# EVGP_Estop_Motherboard.net
KiCad netlist of a schematic drawn in EAGLE
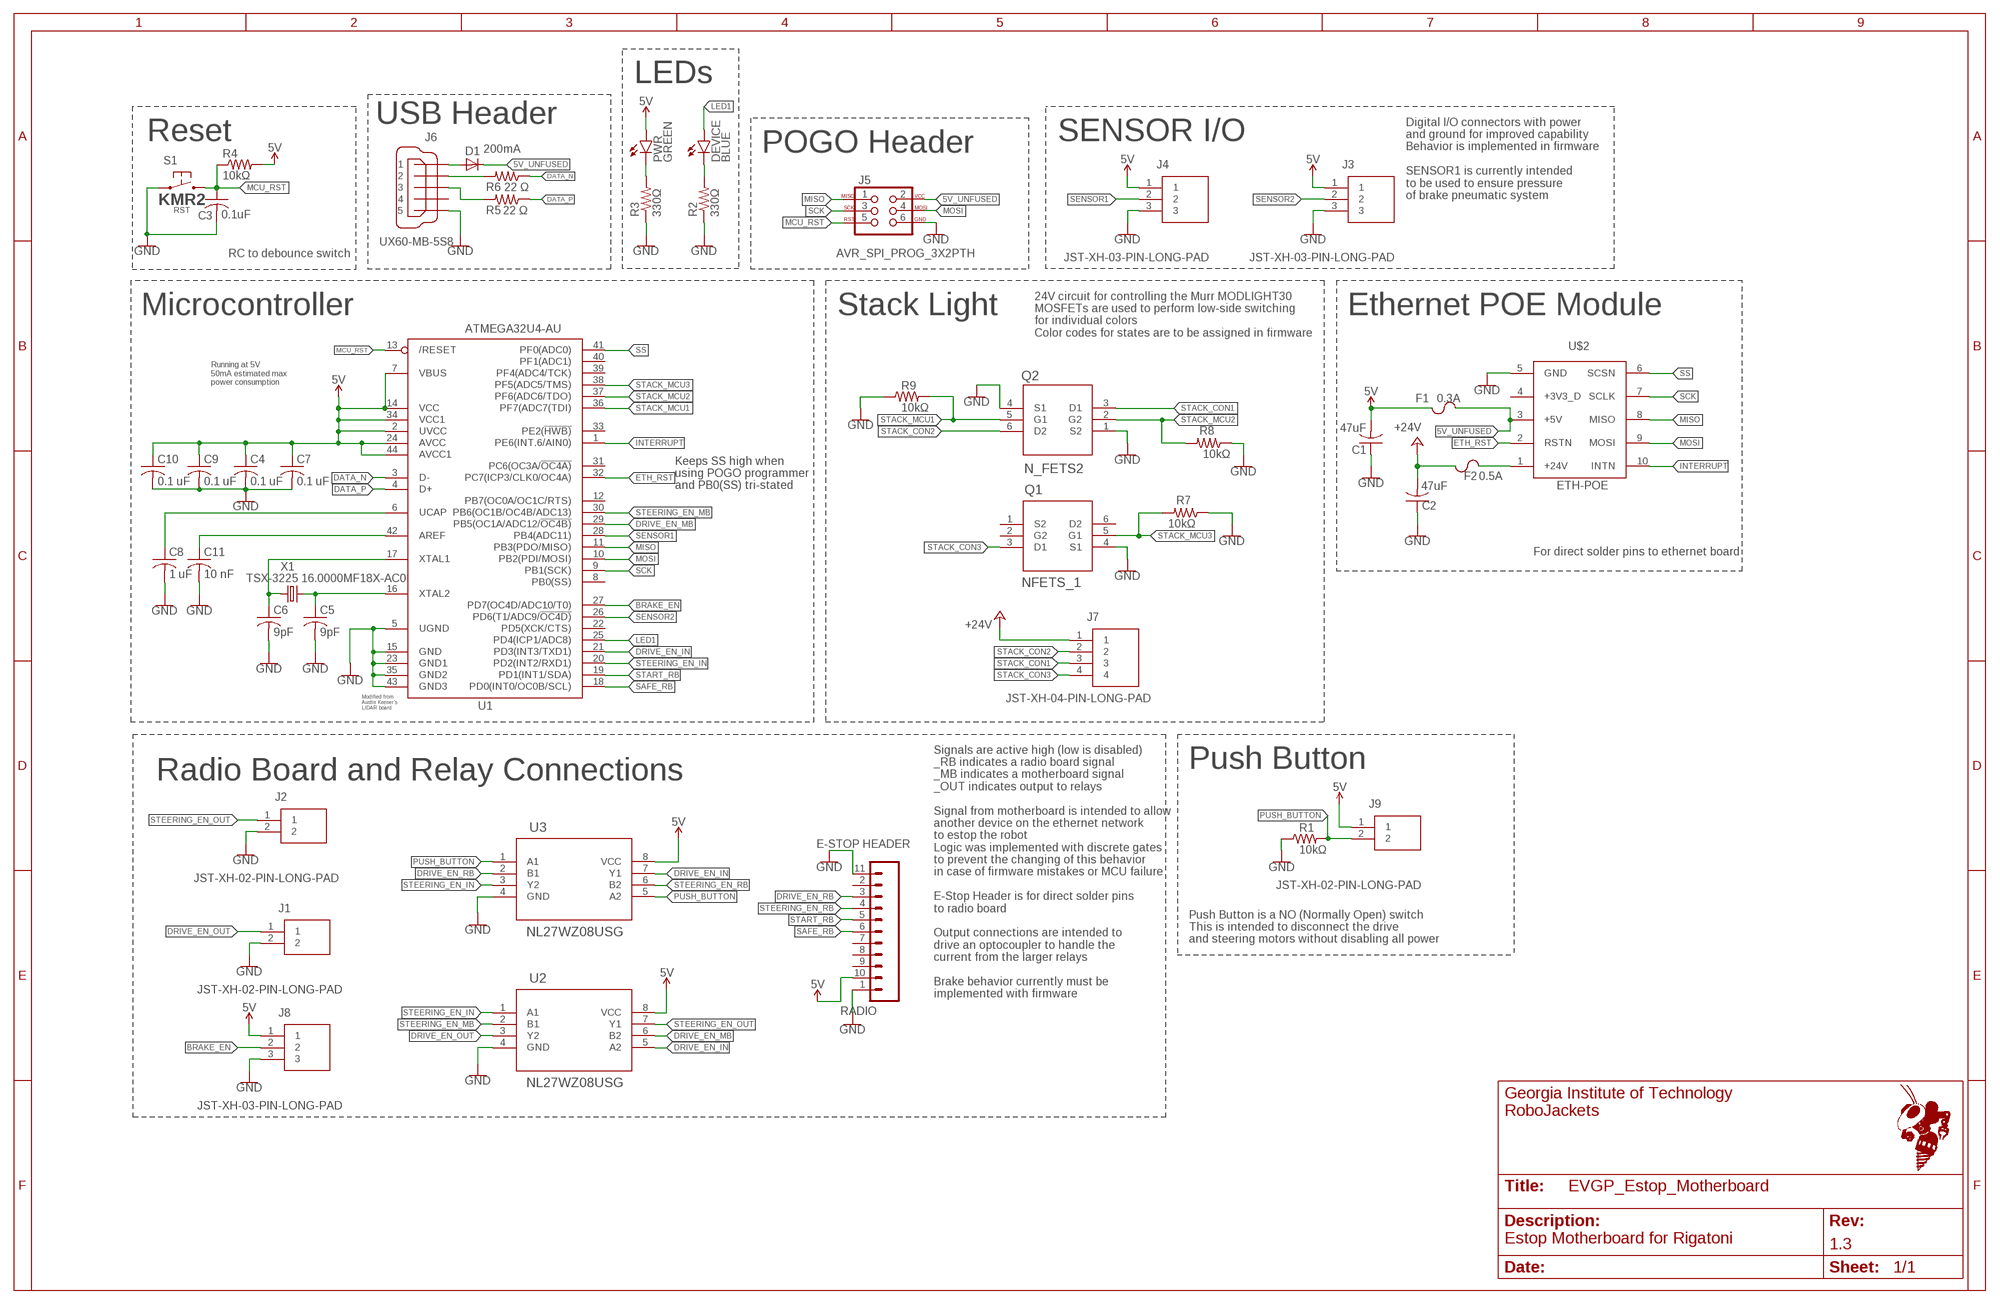
[diagram p0: schematic, sheet 1]

(export (version "E")
  (design (tool "Eeschema 10.0.6"))
  (components
    (comp (ref "C1")
      (value "47uF")
      (footprint "eagle-import:C1206")
      (libsource (lib "eagle-import") (part "C-USC1206"))
    )
    (comp (ref "C2")
      (value "47uF")
      (footprint "eagle-import:C1206")
      (libsource (lib "eagle-import") (part "C-USC1206"))
    )
    (comp (ref "C3")
      (value "0.1uF")
      (footprint "eagle-import:C0603")
      (libsource (lib "eagle-import") (part "C-USC0603"))
    )
    (comp (ref "C4")
      (value "0.1 uF")
      (footprint "eagle-import:C0603")
      (libsource (lib "eagle-import") (part "resistor_348_C-USC0603"))
    )
    (comp (ref "C5")
      (value "9pF")
      (footprint "eagle-import:C0603")
      (libsource (lib "eagle-import") (part "resistor_348_C-USC0603"))
    )
    (comp (ref "C6")
      (value "9pF")
      (footprint "eagle-import:C0603")
      (libsource (lib "eagle-import") (part "resistor_348_C-USC0603"))
    )
    (comp (ref "C7")
      (value "0.1 uF")
      (footprint "eagle-import:C0603")
      (libsource (lib "eagle-import") (part "resistor_348_C-USC0603"))
    )
    (comp (ref "C8")
      (value "1 uF")
      (footprint "eagle-import:C0603")
      (libsource (lib "eagle-import") (part "resistor_348_C-USC0603"))
    )
    (comp (ref "C9")
      (value "0.1 uF")
      (footprint "eagle-import:C0603")
      (libsource (lib "eagle-import") (part "resistor_348_C-USC0603"))
    )
    (comp (ref "C10")
      (value "0.1 uF")
      (footprint "eagle-import:C0603")
      (libsource (lib "eagle-import") (part "resistor_348_C-USC0603"))
    )
    (comp (ref "C11")
      (value "10 nF")
      (footprint "eagle-import:C0603")
      (libsource (lib "eagle-import") (part "resistor_348_C-USC0603"))
    )
    (comp (ref "D1")
      (value "200mA")
      (footprint "eagle-import:SOD323-R")
      (libsource (lib "eagle-import") (part "DIODE-SOD323-R"))
    )
    (comp (ref "DEVICE")
      (value "BLUE")
      (footprint "eagle-import:CHIP-LED0603")
      (libsource (lib "eagle-import") (part "LEDCHIP-LED0603"))
    )
    (comp (ref "F1")
      (value "0.3A")
      (footprint "eagle-import:F1206")
      (libsource (lib "eagle-import") (part "CHIP_FUSE1206"))
    )
    (comp (ref "F2")
      (value "0.5A")
      (footprint "eagle-import:F1206")
      (libsource (lib "eagle-import") (part "CHIP_FUSE1206"))
    )
    (comp (ref "J1")
      (value "JST-XH-02-PIN-LONG-PAD")
      (footprint "eagle-import:JST-XH-02-PACKAGE-LONG-PAD")
      (libsource (lib "eagle-import") (part "JST-XH-02-PIN-LONG-PAD"))
    )
    (comp (ref "J2")
      (value "JST-XH-02-PIN-LONG-PAD")
      (footprint "eagle-import:JST-XH-02-PACKAGE-LONG-PAD")
      (libsource (lib "eagle-import") (part "JST-XH-02-PIN-LONG-PAD"))
    )
    (comp (ref "J3")
      (value "JST-XH-03-PIN-LONG-PAD")
      (footprint "eagle-import:JST-XH-03-PACKAGE-LONG-PAD")
      (libsource (lib "eagle-import") (part "JST-XH-03-PIN-LONG-PAD"))
    )
    (comp (ref "J4")
      (value "JST-XH-03-PIN-LONG-PAD")
      (footprint "eagle-import:JST-XH-03-PACKAGE-LONG-PAD")
      (libsource (lib "eagle-import") (part "JST-XH-03-PIN-LONG-PAD"))
    )
    (comp (ref "J5")
      (value "AVR_SPI_PROG_3X2PTH")
      (footprint "eagle-import:2X3")
      (libsource (lib "eagle-import") (part "AVR_SPI_PROG_3X2PTH"))
    )
    (comp (ref "J6")
      (value "UX60-MB-5S8")
      (footprint "eagle-import:UX60-MB-5S8")
      (libsource (lib "eagle-import") (part "UX60-MB-5S?8"))
    )
    (comp (ref "J7")
      (value "JST-XH-04-PIN-LONG-PAD")
      (footprint "eagle-import:JST-XH-04-PACKAGE-LONG-PAD")
      (libsource (lib "eagle-import") (part "JST-XH-04-PIN-LONG-PAD"))
    )
    (comp (ref "J8")
      (value "JST-XH-03-PIN-LONG-PAD")
      (footprint "eagle-import:JST-XH-03-PACKAGE-LONG-PAD")
      (libsource (lib "eagle-import") (part "JST-XH-03-PIN-LONG-PAD"))
    )
    (comp (ref "J9")
      (value "JST-XH-02-PIN-LONG-PAD")
      (footprint "eagle-import:JST-XH-02-PACKAGE-LONG-PAD")
      (libsource (lib "eagle-import") (part "JST-XH-02-PIN-LONG-PAD"))
    )
    (comp (ref "PWR")
      (value "GREEN")
      (footprint "eagle-import:CHIP-LED0603")
      (libsource (lib "eagle-import") (part "LEDCHIP-LED0603"))
    )
    (comp (ref "Q1")
      (value "NFETS_1")
      (footprint "eagle-import:SOT-363")
      (fields (field (name "MANUFACTURER_PART_NUMBER") "BSS84DW7F"))
      (libsource (lib "eagle-import") (part "BSS84DW-7-F"))
    )
    (comp (ref "Q2")
      (value "N_FETS2")
      (footprint "eagle-import:SOT-363")
      (fields (field (name "MANUFACTURER_PART_NUMBER") "BSS84DW7F"))
      (libsource (lib "eagle-import") (part "BSS84DW-7-F"))
    )
    (comp (ref "R1")
      (value "10kΩ")
      (footprint "eagle-import:R0603")
      (libsource (lib "eagle-import") (part "R-US_R0603"))
    )
    (comp (ref "R2")
      (value "330Ω")
      (footprint "eagle-import:R0603")
      (libsource (lib "eagle-import") (part "R-US_R0603"))
    )
    (comp (ref "R3")
      (value "330Ω")
      (footprint "eagle-import:R0603")
      (libsource (lib "eagle-import") (part "R-US_R0603"))
    )
    (comp (ref "R4")
      (value "10kΩ")
      (footprint "eagle-import:R0603")
      (libsource (lib "eagle-import") (part "R-US_R0603"))
    )
    (comp (ref "R5")
      (value "22 Ω")
      (footprint "eagle-import:R0603")
      (libsource (lib "eagle-import") (part "R-US_R0603"))
    )
    (comp (ref "R6")
      (value "22 Ω")
      (footprint "eagle-import:R0603")
      (libsource (lib "eagle-import") (part "R-US_R0603"))
    )
    (comp (ref "R7")
      (value "10kΩ")
      (footprint "eagle-import:R0603")
      (libsource (lib "eagle-import") (part "R-US_R0603"))
    )
    (comp (ref "R8")
      (value "10kΩ")
      (footprint "eagle-import:R0603")
      (libsource (lib "eagle-import") (part "R-US_R0603"))
    )
    (comp (ref "R9")
      (value "10kΩ")
      (footprint "eagle-import:R0603")
      (libsource (lib "eagle-import") (part "R-US_R0603"))
    )
    (comp (ref "RADIO")
      (value "E-STOP HEADER")
      (footprint "eagle-import:RADIO_V1.3")
      (libsource (lib "eagle-import") (part "ESTOP_RADIO"))
    )
    (comp (ref "S1")
      (value "KMR2")
      (footprint "eagle-import:KMR2")
      (fields (field (name "FUNCTION") "Reset") (field (name "FUNCTION_1") "RST"))
      (libsource (lib "eagle-import") (part "KMR2"))
    )
    (comp (ref "U$2")
      (value "ETH-POE")
      (footprint "eagle-import:HDRVR10W64P4000X254_2X5_1016X508X254B")
      (libsource (lib "eagle-import") (part "ETH-POE"))
    )
    (comp (ref "U1")
      (value "ATMEGA32U4-AU")
      (footprint "eagle-import:TQFP44")
      (libsource (lib "eagle-import") (part "ATMEGA32U4-AU"))
    )
    (comp (ref "U2")
      (value "NL27WZ08USG")
      (footprint "eagle-import:US8_2P40X2P10")
      (libsource (lib "eagle-import") (part "NL27WZ08USG"))
    )
    (comp (ref "U3")
      (value "NL27WZ08USG")
      (footprint "eagle-import:US8_2P40X2P10")
      (libsource (lib "eagle-import") (part "NL27WZ08USG"))
    )
    (comp (ref "X1")
      (value "TSX-3225 16.0000MF18X-AC0")
      (footprint "eagle-import:XTAL-3.2X2.5")
      (libsource (lib "eagle-import") (part "XTAL-3.2X2.5"))
    )
  )
  (nets
    (net (code "1") (name "+24V") (class "Default")
      (node (ref "C2") (pin "2") (pinfunction "2_2") (pintype "passive"))
      (node (ref "F2") (pin "1") (pinfunction "1_1") (pintype "bidirectional"))
      (node (ref "J7") (pin "1") (pinfunction "1_1") (pintype "bidirectional"))
    )
    (net (code "2") (name "5V") (class "Default")
      (node (ref "C1") (pin "2") (pinfunction "2_2") (pintype "passive"))
      (node (ref "C10") (pin "1") (pinfunction "1_1") (pintype "passive"))
      (node (ref "C4") (pin "1") (pinfunction "1_1") (pintype "passive"))
      (node (ref "C7") (pin "1") (pinfunction "1_1") (pintype "passive"))
      (node (ref "C9") (pin "1") (pinfunction "1_1") (pintype "passive"))
      (node (ref "F1") (pin "1") (pinfunction "1_1") (pintype "bidirectional"))
      (node (ref "J3") (pin "1") (pinfunction "1_1") (pintype "bidirectional"))
      (node (ref "J4") (pin "1") (pinfunction "1_1") (pintype "bidirectional"))
      (node (ref "J8") (pin "1") (pinfunction "1_1") (pintype "bidirectional"))
      (node (ref "J9") (pin "1") (pinfunction "1_1") (pintype "bidirectional"))
      (node (ref "PWR") (pin "A") (pinfunction "A_A") (pintype "passive"))
      (node (ref "R4") (pin "2") (pinfunction "2_2") (pintype "passive"))
      (node (ref "RADIO") (pin "10") (pinfunction "5V_10") (pintype "passive"))
      (node (ref "U1") (pin "14") (pinfunction "VCC_14") (pintype "bidirectional"))
      (node (ref "U1") (pin "2") (pinfunction "UVCC_2") (pintype "bidirectional"))
      (node (ref "U1") (pin "24") (pinfunction "AVCC_24") (pintype "bidirectional"))
      (node (ref "U1") (pin "34") (pinfunction "VCC1_34") (pintype "bidirectional"))
      (node (ref "U1") (pin "44") (pinfunction "AVCC1_44") (pintype "bidirectional"))
      (node (ref "U1") (pin "7") (pinfunction "VBUS_7") (pintype "bidirectional"))
      (node (ref "U2") (pin "8") (pinfunction "VCC_8") (pintype "power_in"))
      (node (ref "U3") (pin "8") (pinfunction "VCC_8") (pintype "power_in"))
    )
    (net (code "3") (name "5V_UNFUSED") (class "Default")
      (node (ref "D1") (pin "C") (pinfunction "C_C") (pintype "passive"))
      (node (ref "F1") (pin "2") (pinfunction "2_2") (pintype "bidirectional"))
      (node (ref "J5") (pin "2") (pinfunction "2_2") (pintype "passive"))
      (node (ref "U$2") (pin "3") (pinfunction "+5V_3") (pintype "bidirectional"))
    )
    (net (code "4") (name "BRAKE_EN") (class "Default")
      (node (ref "J8") (pin "2") (pinfunction "2_2") (pintype "bidirectional"))
      (node (ref "U1") (pin "27") (pinfunction "PD7(OC4D/ADC10/T0)_27") (pintype "bidirectional"))
    )
    (net (code "5") (name "DATA_N") (class "Default")
      (node (ref "R6") (pin "1") (pinfunction "1_1") (pintype "passive"))
      (node (ref "U1") (pin "3") (pinfunction "D-_3") (pintype "bidirectional"))
    )
    (net (code "6") (name "DATA_P") (class "Default")
      (node (ref "R5") (pin "1") (pinfunction "1_1") (pintype "passive"))
      (node (ref "U1") (pin "4") (pinfunction "D+_4") (pintype "bidirectional"))
    )
    (net (code "7") (name "DRIVE_EN_IN") (class "Default")
      (node (ref "U1") (pin "21") (pinfunction "PD3(INT3/TXD1)_21") (pintype "bidirectional"))
      (node (ref "U2") (pin "5") (pinfunction "A2_5") (pintype "input"))
      (node (ref "U3") (pin "7") (pinfunction "Y1_7") (pintype "output"))
    )
    (net (code "8") (name "DRIVE_EN_MB") (class "Default")
      (node (ref "U1") (pin "29") (pinfunction "PB5(OC1A/ADC12/~{OC4B})_29") (pintype "bidirectional"))
      (node (ref "U2") (pin "6") (pinfunction "B2_6") (pintype "input"))
    )
    (net (code "9") (name "DRIVE_EN_OUT") (class "Default")
      (node (ref "J1") (pin "1") (pinfunction "1_1") (pintype "bidirectional"))
      (node (ref "U2") (pin "3") (pinfunction "Y2_3") (pintype "output"))
    )
    (net (code "10") (name "DRIVE_EN_RB") (class "Default")
      (node (ref "RADIO") (pin "3") (pinfunction "D1_3") (pintype "passive"))
      (node (ref "U3") (pin "2") (pinfunction "B1_2") (pintype "input"))
    )
    (net (code "11") (name "ETH_RST") (class "Default")
      (node (ref "U$2") (pin "2") (pinfunction "RSTN_2") (pintype "bidirectional"))
      (node (ref "U1") (pin "32") (pinfunction "PC7(ICP3/CLK0/OC4A)_32") (pintype "bidirectional"))
    )
    (net (code "12") (name "GND") (class "Default")
      (node (ref "C1") (pin "1") (pinfunction "1_1") (pintype "passive"))
      (node (ref "C10") (pin "2") (pinfunction "2_2") (pintype "passive"))
      (node (ref "C11") (pin "2") (pinfunction "2_2") (pintype "passive"))
      (node (ref "C2") (pin "1") (pinfunction "1_1") (pintype "passive"))
      (node (ref "C3") (pin "2") (pinfunction "2_2") (pintype "passive"))
      (node (ref "C4") (pin "2") (pinfunction "2_2") (pintype "passive"))
      (node (ref "C5") (pin "2") (pinfunction "2_2") (pintype "passive"))
      (node (ref "C6") (pin "2") (pinfunction "2_2") (pintype "passive"))
      (node (ref "C7") (pin "2") (pinfunction "2_2") (pintype "passive"))
      (node (ref "C8") (pin "2") (pinfunction "2_2") (pintype "passive"))
      (node (ref "C9") (pin "2") (pinfunction "2_2") (pintype "passive"))
      (node (ref "J1") (pin "2") (pinfunction "2_2") (pintype "bidirectional"))
      (node (ref "J2") (pin "2") (pinfunction "2_2") (pintype "bidirectional"))
      (node (ref "J3") (pin "3") (pinfunction "3_3") (pintype "bidirectional"))
      (node (ref "J4") (pin "3") (pinfunction "3_3") (pintype "bidirectional"))
      (node (ref "J5") (pin "6") (pinfunction "6_6") (pintype "passive"))
      (node (ref "J6") (pin "5") (pinfunction "5_5") (pintype "passive"))
      (node (ref "J8") (pin "3") (pinfunction "3_3") (pintype "bidirectional"))
      (node (ref "Q1") (pin "4") (pinfunction "S1_4") (pintype "passive"))
      (node (ref "Q2") (pin "1") (pinfunction "S2_1") (pintype "passive"))
      (node (ref "Q2") (pin "4") (pinfunction "S1_4") (pintype "passive"))
      (node (ref "R1") (pin "1") (pinfunction "1_1") (pintype "passive"))
      (node (ref "R2") (pin "1") (pinfunction "1_1") (pintype "passive"))
      (node (ref "R3") (pin "1") (pinfunction "1_1") (pintype "passive"))
      (node (ref "R7") (pin "1") (pinfunction "1_1") (pintype "passive"))
      (node (ref "R8") (pin "1") (pinfunction "1_1") (pintype "passive"))
      (node (ref "R9") (pin "1") (pinfunction "1_1") (pintype "passive"))
      (node (ref "RADIO") (pin "1") (pinfunction "GND_1") (pintype "passive"))
      (node (ref "RADIO") (pin "11") (pinfunction "GND_11") (pintype "passive"))
      (node (ref "S1") (pin "1.1") (pinfunction "1_1.1") (pintype "passive"))
      (node (ref "S1") (pin "1.2") (pinfunction "1_1.2") (pintype "passive"))
      (node (ref "U$2") (pin "5") (pinfunction "GND_5") (pintype "bidirectional"))
      (node (ref "U1") (pin "15") (pinfunction "GND_15") (pintype "bidirectional"))
      (node (ref "U1") (pin "23") (pinfunction "GND1_23") (pintype "bidirectional"))
      (node (ref "U1") (pin "35") (pinfunction "GND2_35") (pintype "bidirectional"))
      (node (ref "U1") (pin "43") (pinfunction "GND3_43") (pintype "bidirectional"))
      (node (ref "U1") (pin "5") (pinfunction "UGND_5") (pintype "bidirectional"))
      (node (ref "U2") (pin "4") (pinfunction "GND_4") (pintype "power_in"))
      (node (ref "U3") (pin "4") (pinfunction "GND_4") (pintype "power_in"))
    )
    (net (code "13") (name "INTERRUPT") (class "Default")
      (node (ref "U$2") (pin "10") (pinfunction "INTN_10") (pintype "bidirectional"))
      (node (ref "U1") (pin "1") (pinfunction "PE6(INT.6/AIN0)_1") (pintype "bidirectional"))
    )
    (net (code "14") (name "LED1") (class "Default")
      (node (ref "DEVICE") (pin "A") (pinfunction "A_A") (pintype "passive"))
      (node (ref "U1") (pin "25") (pinfunction "PD4(ICP1/ADC8)_25") (pintype "bidirectional"))
    )
    (net (code "15") (name "MCU_RST") (class "Default")
      (node (ref "C3") (pin "1") (pinfunction "1_1") (pintype "passive"))
      (node (ref "J5") (pin "5") (pinfunction "5_5") (pintype "passive"))
      (node (ref "R4") (pin "1") (pinfunction "1_1") (pintype "passive"))
      (node (ref "S1") (pin "2.1") (pinfunction "2_2.1") (pintype "passive"))
      (node (ref "S1") (pin "2.2") (pinfunction "2_2.2") (pintype "passive"))
      (node (ref "U1") (pin "13") (pinfunction "/RESET_13") (pintype "bidirectional"))
    )
    (net (code "16") (name "MISO") (class "Default")
      (node (ref "J5") (pin "1") (pinfunction "1_1") (pintype "passive"))
      (node (ref "U$2") (pin "8") (pinfunction "MISO_8") (pintype "bidirectional"))
      (node (ref "U1") (pin "11") (pinfunction "PB3(PDO/MISO)_11") (pintype "bidirectional"))
    )
    (net (code "17") (name "MOSI") (class "Default")
      (node (ref "J5") (pin "4") (pinfunction "4_4") (pintype "passive"))
      (node (ref "U$2") (pin "9") (pinfunction "MOSI_9") (pintype "bidirectional"))
      (node (ref "U1") (pin "10") (pinfunction "PB2(PDI/MOSI)_10") (pintype "bidirectional"))
    )
    (net (code "18") (name "Net-(D1-PadA)") (class "Default")
      (node (ref "D1") (pin "A") (pinfunction "A_A") (pintype "passive"))
      (node (ref "J6") (pin "1") (pinfunction "1_1") (pintype "passive"))
    )
    (net (code "19") (name "Net-(DEVICE-PadC)") (class "Default")
      (node (ref "DEVICE") (pin "C") (pinfunction "C_C") (pintype "passive"))
      (node (ref "R2") (pin "2") (pinfunction "2_2") (pintype "passive"))
    )
    (net (code "20") (name "Net-(J6-Pad2)") (class "Default")
      (node (ref "J6") (pin "2") (pinfunction "2_2") (pintype "passive"))
      (node (ref "R6") (pin "2") (pinfunction "2_2") (pintype "passive"))
    )
    (net (code "21") (name "Net-(J6-Pad3)") (class "Default")
      (node (ref "J6") (pin "3") (pinfunction "3_3") (pintype "passive"))
      (node (ref "R5") (pin "2") (pinfunction "2_2") (pintype "passive"))
    )
    (net (code "22") (name "Net-(PWR-PadC)") (class "Default")
      (node (ref "PWR") (pin "C") (pinfunction "C_C") (pintype "passive"))
      (node (ref "R3") (pin "2") (pinfunction "2_2") (pintype "passive"))
    )
    (net (code "23") (name "Net-(U$2-+24V)") (class "Default")
      (node (ref "F2") (pin "2") (pinfunction "2_2") (pintype "bidirectional"))
      (node (ref "U$2") (pin "1") (pinfunction "+24V_1") (pintype "bidirectional"))
    )
    (net (code "24") (name "Net-(U1-AREF)") (class "Default")
      (node (ref "C11") (pin "1") (pinfunction "1_1") (pintype "passive"))
      (node (ref "U1") (pin "42") (pinfunction "AREF_42") (pintype "bidirectional"))
    )
    (net (code "25") (name "Net-(U1-UCAP)") (class "Default")
      (node (ref "C8") (pin "1") (pinfunction "1_1") (pintype "passive"))
      (node (ref "U1") (pin "6") (pinfunction "UCAP_6") (pintype "bidirectional"))
    )
    (net (code "26") (name "Net-(U1-XTAL1)") (class "Default")
      (node (ref "C6") (pin "1") (pinfunction "1_1") (pintype "passive"))
      (node (ref "U1") (pin "17") (pinfunction "XTAL1_17") (pintype "bidirectional"))
      (node (ref "X1") (pin "1") (pinfunction "1_1") (pintype "passive"))
    )
    (net (code "27") (name "Net-(U1-XTAL2)") (class "Default")
      (node (ref "C5") (pin "1") (pinfunction "1_1") (pintype "passive"))
      (node (ref "U1") (pin "16") (pinfunction "XTAL2_16") (pintype "bidirectional"))
      (node (ref "X1") (pin "3") (pinfunction "2_3") (pintype "passive"))
    )
    (net (code "28") (name "PUSH_BUTTON") (class "Default")
      (node (ref "J9") (pin "2") (pinfunction "2_2") (pintype "bidirectional"))
      (node (ref "R1") (pin "2") (pinfunction "2_2") (pintype "passive"))
      (node (ref "U3") (pin "1") (pinfunction "A1_1") (pintype "input"))
      (node (ref "U3") (pin "5") (pinfunction "A2_5") (pintype "input"))
    )
    (net (code "29") (name "SAFE_RB") (class "Default")
      (node (ref "RADIO") (pin "6") (pinfunction "D4_6") (pintype "passive"))
      (node (ref "U1") (pin "18") (pinfunction "PD0(INT0/OC0B/SCL)_18") (pintype "bidirectional"))
    )
    (net (code "30") (name "SCK") (class "Default")
      (node (ref "J5") (pin "3") (pinfunction "3_3") (pintype "passive"))
      (node (ref "U$2") (pin "7") (pinfunction "SCLK_7") (pintype "bidirectional"))
      (node (ref "U1") (pin "9") (pinfunction "PB1(SCK)_9") (pintype "bidirectional"))
    )
    (net (code "31") (name "SENSOR1") (class "Default")
      (node (ref "J4") (pin "2") (pinfunction "2_2") (pintype "bidirectional"))
      (node (ref "U1") (pin "28") (pinfunction "PB4(ADC11)_28") (pintype "bidirectional"))
    )
    (net (code "32") (name "SENSOR2") (class "Default")
      (node (ref "J3") (pin "2") (pinfunction "2_2") (pintype "bidirectional"))
      (node (ref "U1") (pin "26") (pinfunction "PD6(T1/ADC9/~{OC4D})_26") (pintype "bidirectional"))
    )
    (net (code "33") (name "SS") (class "Default")
      (node (ref "U$2") (pin "6") (pinfunction "SCSN_6") (pintype "bidirectional"))
      (node (ref "U1") (pin "41") (pinfunction "PF0(ADC0)_41") (pintype "bidirectional"))
    )
    (net (code "34") (name "STACK_CON1") (class "Default")
      (node (ref "J7") (pin "3") (pinfunction "3_3") (pintype "bidirectional"))
      (node (ref "Q2") (pin "3") (pinfunction "D1_3") (pintype "passive"))
    )
    (net (code "35") (name "STACK_CON2") (class "Default")
      (node (ref "J7") (pin "2") (pinfunction "2_2") (pintype "bidirectional"))
      (node (ref "Q2") (pin "6") (pinfunction "D2_6") (pintype "passive"))
    )
    (net (code "36") (name "STACK_CON3") (class "Default")
      (node (ref "J7") (pin "4") (pinfunction "4_4") (pintype "bidirectional"))
      (node (ref "Q1") (pin "3") (pinfunction "D1_3") (pintype "passive"))
    )
    (net (code "37") (name "STACK_MCU1") (class "Default")
      (node (ref "Q2") (pin "5") (pinfunction "G1_5") (pintype "passive"))
      (node (ref "R9") (pin "2") (pinfunction "2_2") (pintype "passive"))
      (node (ref "U1") (pin "36") (pinfunction "PF7(ADC7(TDI)_36") (pintype "bidirectional"))
    )
    (net (code "38") (name "STACK_MCU2") (class "Default")
      (node (ref "Q2") (pin "2") (pinfunction "G2_2") (pintype "passive"))
      (node (ref "R8") (pin "2") (pinfunction "2_2") (pintype "passive"))
      (node (ref "U1") (pin "37") (pinfunction "PF6(ADC6/TDO)_37") (pintype "bidirectional"))
    )
    (net (code "39") (name "STACK_MCU3") (class "Default")
      (node (ref "Q1") (pin "5") (pinfunction "G1_5") (pintype "passive"))
      (node (ref "R7") (pin "2") (pinfunction "2_2") (pintype "passive"))
      (node (ref "U1") (pin "38") (pinfunction "PF5(ADC5/TMS)_38") (pintype "bidirectional"))
    )
    (net (code "40") (name "START_RB") (class "Default")
      (node (ref "RADIO") (pin "5") (pinfunction "D3_5") (pintype "passive"))
      (node (ref "U1") (pin "19") (pinfunction "PD1(INT1/SDA)_19") (pintype "bidirectional"))
    )
    (net (code "41") (name "STEERING_EN_IN") (class "Default")
      (node (ref "U1") (pin "20") (pinfunction "PD2(INT2/RXD1)_20") (pintype "bidirectional"))
      (node (ref "U2") (pin "1") (pinfunction "A1_1") (pintype "input"))
      (node (ref "U3") (pin "3") (pinfunction "Y2_3") (pintype "output"))
    )
    (net (code "42") (name "STEERING_EN_MB") (class "Default")
      (node (ref "U1") (pin "30") (pinfunction "PB6(OC1B/OC4B/ADC13)_30") (pintype "bidirectional"))
      (node (ref "U2") (pin "2") (pinfunction "B1_2") (pintype "input"))
    )
    (net (code "43") (name "STEERING_EN_OUT") (class "Default")
      (node (ref "J2") (pin "1") (pinfunction "1_1") (pintype "bidirectional"))
      (node (ref "U2") (pin "7") (pinfunction "Y1_7") (pintype "output"))
    )
    (net (code "44") (name "STEERING_EN_RB") (class "Default")
      (node (ref "RADIO") (pin "4") (pinfunction "D2_4") (pintype "passive"))
      (node (ref "U3") (pin "6") (pinfunction "B2_6") (pintype "input"))
    )
    (net (code "45") (name "unconnected-(J6-Pad4)") (class "Default")
      (node (ref "J6") (pin "4") (pinfunction "4_4") (pintype "passive"))
    )
    (net (code "46") (name "unconnected-(Q1-D2-Pad6)") (class "Default")
      (node (ref "Q1") (pin "6") (pinfunction "D2_6") (pintype "passive"))
    )
    (net (code "47") (name "unconnected-(Q1-G2-Pad2)") (class "Default")
      (node (ref "Q1") (pin "2") (pinfunction "G2_2") (pintype "passive"))
    )
    (net (code "48") (name "unconnected-(Q1-S2-Pad1)") (class "Default")
      (node (ref "Q1") (pin "1") (pinfunction "S2_1") (pintype "passive"))
    )
    (net (code "49") (name "unconnected-(RADIO-D5-Pad7)") (class "Default")
      (node (ref "RADIO") (pin "7") (pinfunction "D5_7") (pintype "passive"))
    )
    (net (code "50") (name "unconnected-(RADIO-D6-Pad8)") (class "Default")
      (node (ref "RADIO") (pin "8") (pinfunction "D6_8") (pintype "passive"))
    )
    (net (code "51") (name "unconnected-(RADIO-D7-Pad9)") (class "Default")
      (node (ref "RADIO") (pin "9") (pinfunction "D7_9") (pintype "passive"))
    )
    (net (code "52") (name "unconnected-(RADIO-RST-Pad2)") (class "Default")
      (node (ref "RADIO") (pin "2") (pinfunction "RST_2") (pintype "passive"))
    )
    (net (code "53") (name "unconnected-(U$2-+3V3_D-Pad4)") (class "Default")
      (node (ref "U$2") (pin "4") (pinfunction "+3V3_D_4") (pintype "bidirectional"))
    )
    (net (code "54") (name "unconnected-(U1-PB0(SS)-Pad8)") (class "Default")
      (node (ref "U1") (pin "8") (pinfunction "PB0(SS)_8") (pintype "bidirectional"))
    )
    (net (code "55") (name "unconnected-(U1-PB7(OC0A{slash}OC1C{slash}RTS)-Pad12)") (class "Default")
      (node (ref "U1") (pin "12") (pinfunction "PB7(OC0A/OC1C/RTS)_12") (pintype "bidirectional"))
    )
    (net (code "56") (name "unconnected-(U1-PC6(OC3A{slash}~{OC4A})-Pad31)") (class "Default")
      (node (ref "U1") (pin "31") (pinfunction "PC6(OC3A/~{OC4A})_31") (pintype "bidirectional"))
    )
    (net (code "57") (name "unconnected-(U1-PD5(XCK{slash}CTS)-Pad22)") (class "Default")
      (node (ref "U1") (pin "22") (pinfunction "PD5(XCK/CTS)_22") (pintype "bidirectional"))
    )
    (net (code "58") (name "unconnected-(U1-PE2(~{HWB})-Pad33)") (class "Default")
      (node (ref "U1") (pin "33") (pinfunction "PE2(~{HWB})_33") (pintype "bidirectional"))
    )
    (net (code "59") (name "unconnected-(U1-PF1(ADC1)-Pad40)") (class "Default")
      (node (ref "U1") (pin "40") (pinfunction "PF1(ADC1)_40") (pintype "bidirectional"))
    )
    (net (code "60") (name "unconnected-(U1-PF4(ADC4{slash}TCK)-Pad39)") (class "Default")
      (node (ref "U1") (pin "39") (pinfunction "PF4(ADC4/TCK)_39") (pintype "bidirectional"))
    )
  )
)
